# WaterTank.net
KiCad netlist of a schematic drawn in EasyEDA
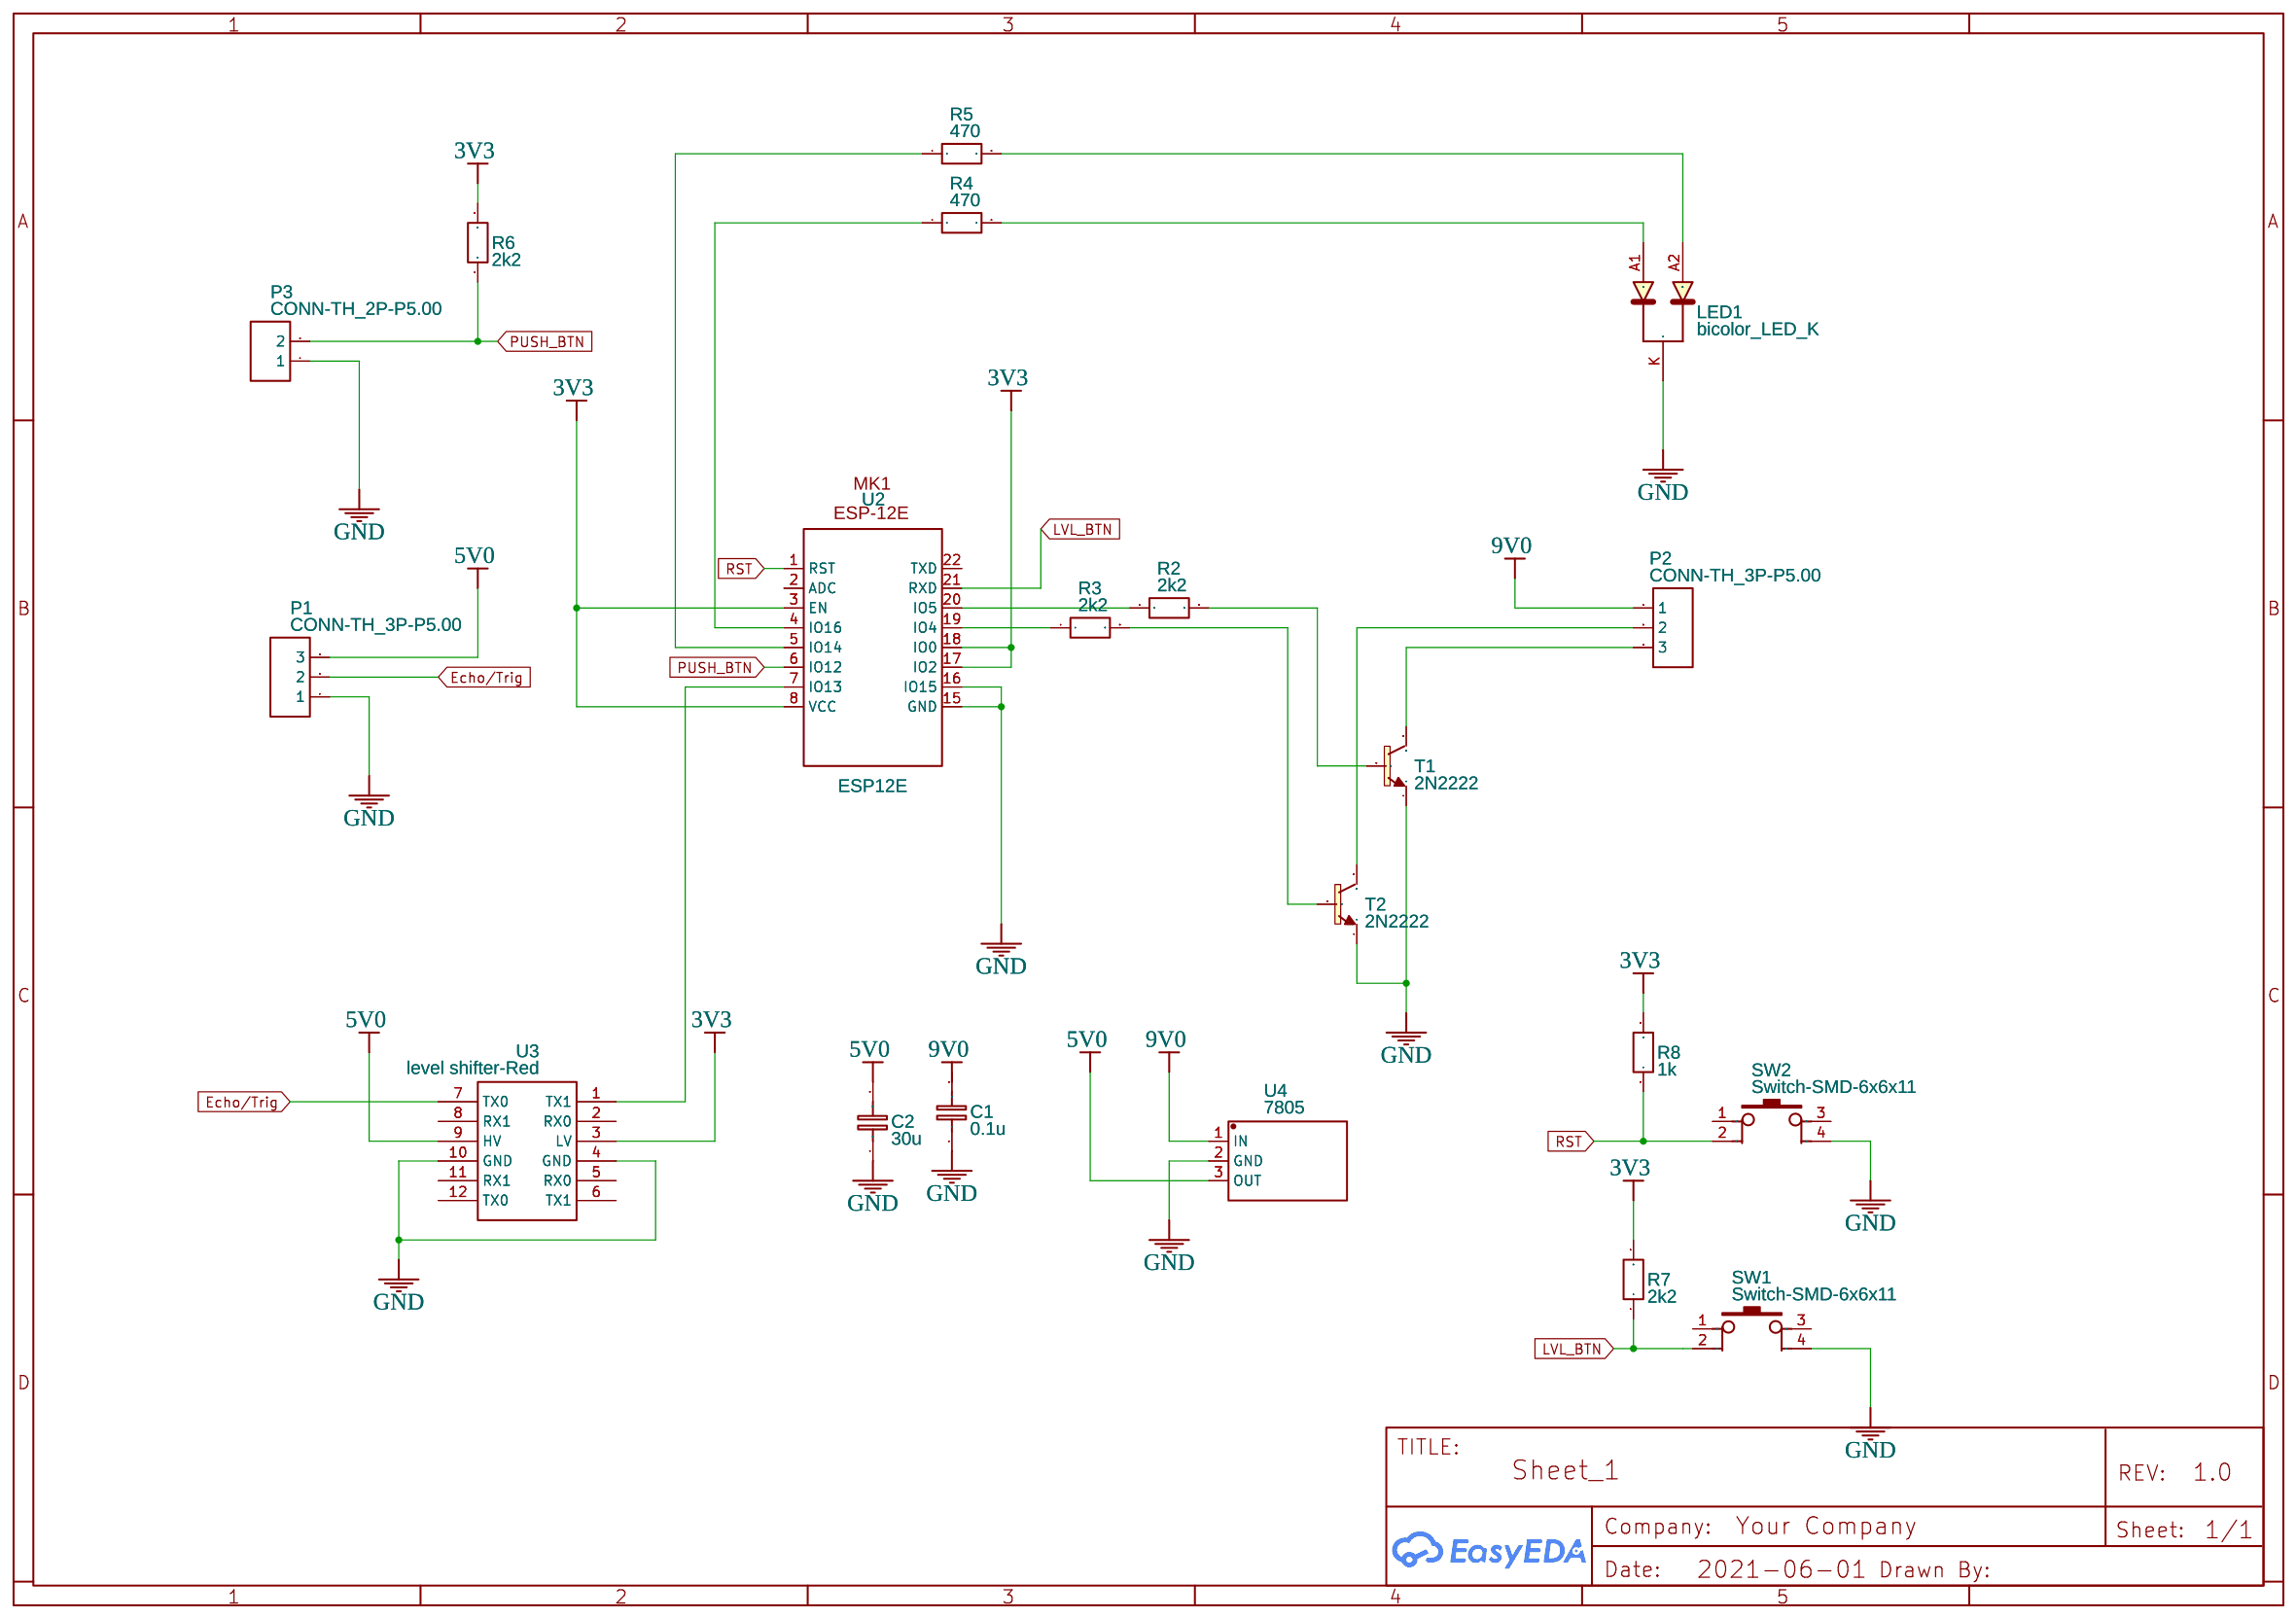
[diagram p0: Main]
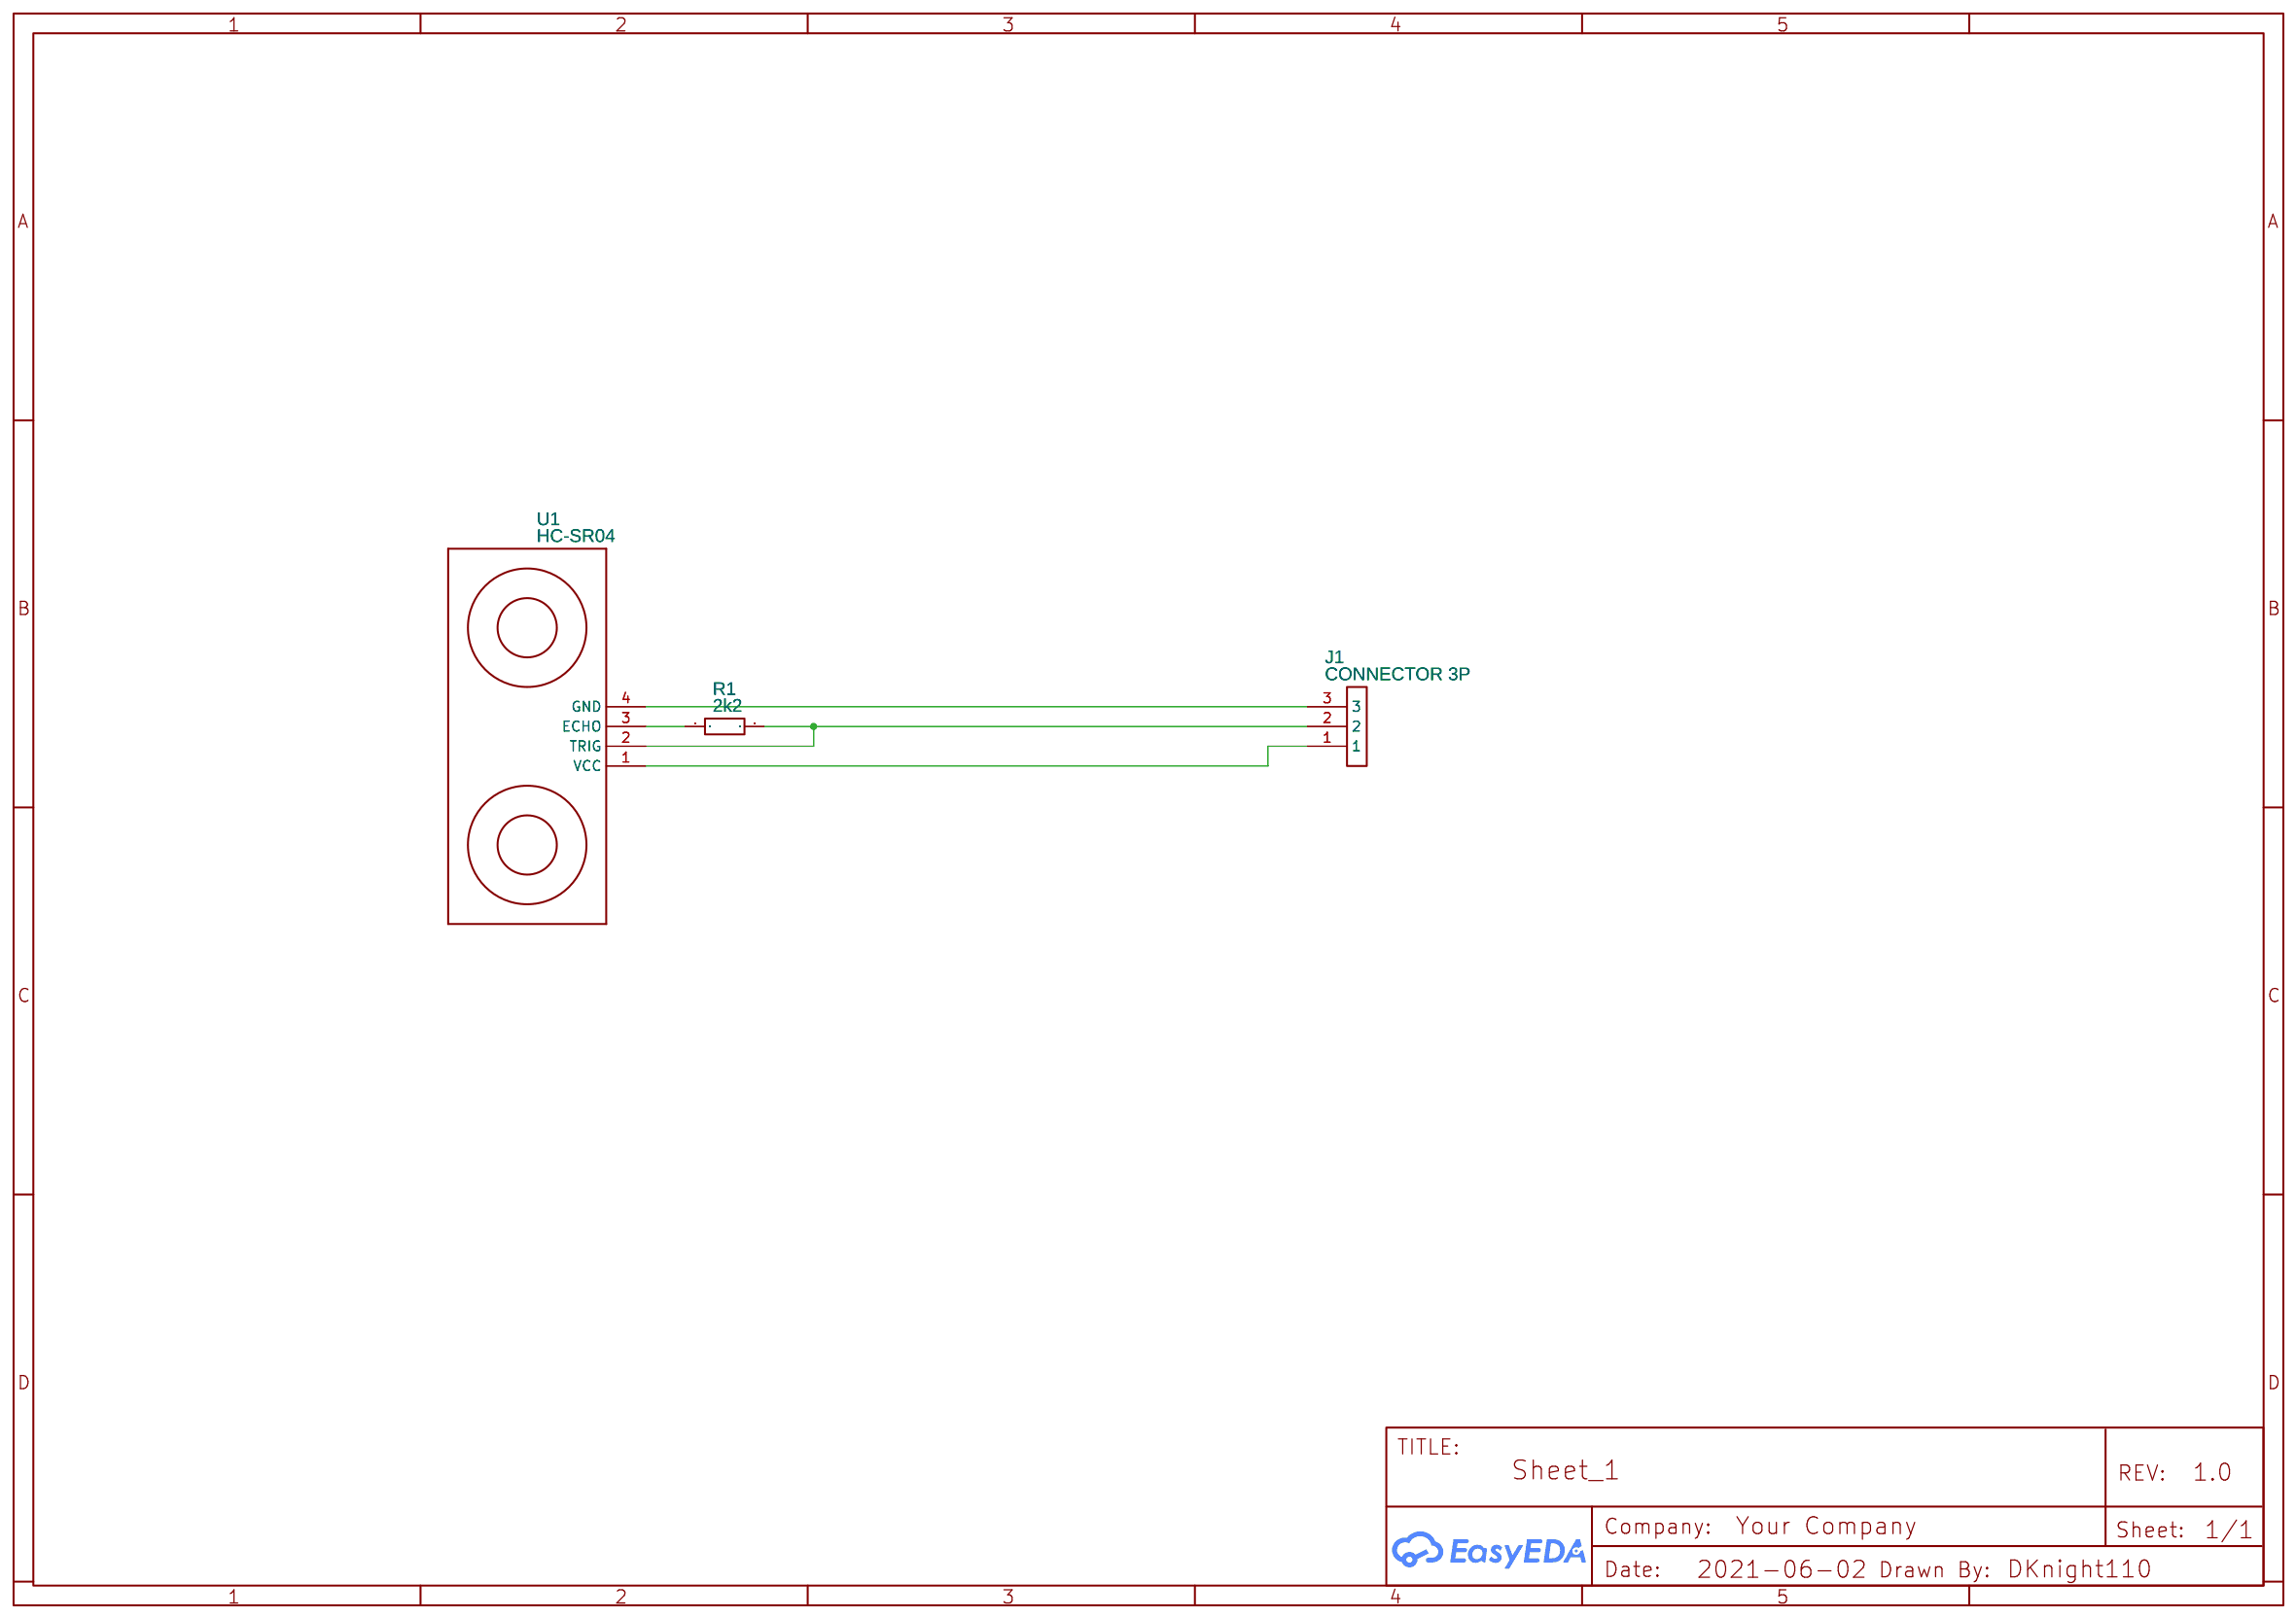
[diagram p1: Water Level Sensor]

(export (version "E")
  (design (tool "Eeschema 10.0.6"))
  (components
    (comp (ref "C1") (value "0.1u") (libsource (lib "") (part "C_0603_EU")))
    (comp (ref "C2") (value "30u") (libsource (lib "") (part "C_0603_EU")))
    (comp (ref "LED1")
      (value "bicolor_LED_K")
      (fields (field (name "BOM_Manufacturer Part") "bicolor LED"))
      (libsource (lib "") (part "bicolor_LED_K"))
    )
    (comp (ref "P1") (value "CONN-TH_3P-P5.00") (libsource (lib "") (part "CONN-TH_3P-P5.00")))
    (comp (ref "P2") (value "CONN-TH_3P-P5.00") (libsource (lib "") (part "CONN-TH_3P-P5.00_1")))
    (comp (ref "P3") (value "CONN-TH_2P-P5.00") (libsource (lib "") (part "CONN-TH_2P-P5.00")))
    (comp (ref "R2") (value "2k2") (libsource (lib "") (part "R_0603_EU")))
    (comp (ref "R3") (value "2k2") (libsource (lib "") (part "R_0603_EU")))
    (comp (ref "R4") (value "470") (libsource (lib "") (part "R_0603_EU")))
    (comp (ref "R5") (value "470") (libsource (lib "") (part "R_0603_EU")))
    (comp (ref "R6") (value "2k2") (libsource (lib "") (part "R_0603_EU_1")))
    (comp (ref "R7") (value "2k2") (libsource (lib "") (part "R_0603_EU_1")))
    (comp (ref "R8") (value "1k") (libsource (lib "") (part "R_0603_EU_1")))
    (comp (ref "SW1")
      (value "Switch-SMD-6x6x11")
      (fields
        (field (name "BOM_Manufacturer Part") "Switch6*6*11")
        (field (name "BOM_Supplier Part") "C91998")
      )
      (libsource (lib "") (part "Switch-SMD-6x6x11"))
    )
    (comp (ref "SW2")
      (value "Switch-SMD-6x6x11")
      (fields
        (field (name "BOM_Manufacturer Part") "Switch6*6*11")
        (field (name "BOM_Supplier Part") "C91998")
      )
      (libsource (lib "") (part "Switch-SMD-6x6x11"))
    )
    (comp (ref "T1") (value "2N2222") (libsource (lib "") (part "2N2222")))
    (comp (ref "T2") (value "2N2222") (libsource (lib "") (part "2N2222")))
    (comp (ref "U2") (value "ESP12E") (libsource (lib "") (part "ESP12E")))
    (comp (ref "U3")
      (value "level shifter-Red")
      (fields (field (name "BOM_Manufacturer Part") "level shifter"))
      (libsource (lib "") (part "level shifter-Red"))
    )
    (comp (ref "U4")
      (value "7805")
      (fields (field (name "BOM_Supplier Part") "C305416"))
      (libsource (lib "") (part "7805"))
    )
    (comp (ref "J1") (value "CONNECTOR 3P") (libsource (lib "") (part "CONNECTOR 3P")))
    (comp (ref "R1")
      (value "2k2")
      (fields
        (field (name "BOM_Manufacturer Part") "CFR02SJ0220A10")
        (field (name "BOM_Supplier Part") "C69874")
      )
      (libsource (lib "") (part "2k2"))
    )
    (comp (ref "U1") (value "HC-SR04") (libsource (lib "") (part "HC-SR04")))
  )
  (nets
    (net (code "1") (name "3V3") (class "Default")
      (node (ref "R6") (pin "2") (pinfunction "2_2") (pintype "unspecified"))
      (node (ref "R7") (pin "2") (pinfunction "2_2") (pintype "unspecified"))
      (node (ref "R8") (pin "2") (pinfunction "2_2") (pintype "unspecified"))
      (node (ref "U2") (pin "17") (pinfunction "IO2_17") (pintype "unspecified"))
      (node (ref "U2") (pin "18") (pinfunction "IO0_18") (pintype "unspecified"))
      (node (ref "U2") (pin "3") (pinfunction "EN_3") (pintype "unspecified"))
      (node (ref "U2") (pin "8") (pinfunction "VCC_8") (pintype "unspecified"))
      (node (ref "U3") (pin "3") (pinfunction "LV_3") (pintype "unspecified"))
    )
    (net (code "2") (name "5V0") (class "Default")
      (node (ref "C2") (pin "2") (pinfunction "2_2") (pintype "unspecified"))
      (node (ref "P1") (pin "3") (pinfunction "3_3") (pintype "unspecified"))
      (node (ref "U3") (pin "9") (pinfunction "HV_9") (pintype "unspecified"))
      (node (ref "U4") (pin "3") (pinfunction "OUT_3") (pintype "unspecified"))
    )
    (net (code "3") (name "9V0") (class "Default")
      (node (ref "P2") (pin "1") (pinfunction "1_1") (pintype "unspecified"))
      (node (ref "U4") (pin "1") (pinfunction "IN_1") (pintype "unspecified"))
    )
    (net (code "4") (name "Echo{slash}Trig") (class "Default")
      (node (ref "P1") (pin "2") (pinfunction "2_2") (pintype "unspecified"))
      (node (ref "U3") (pin "7") (pinfunction "TX0_7") (pintype "unspecified"))
    )
    (net (code "5") (name "GND") (class "Default")
      (node (ref "C1") (pin "1") (pinfunction "1_1") (pintype "unspecified"))
      (node (ref "C2") (pin "1") (pinfunction "1_1") (pintype "unspecified"))
      (node (ref "LED1") (pin "K") (pinfunction "K_K") (pintype "unspecified"))
      (node (ref "P1") (pin "1") (pinfunction "1_1") (pintype "unspecified"))
      (node (ref "P3") (pin "1") (pinfunction "1_1") (pintype "unspecified"))
      (node (ref "SW1") (pin "4") (pinfunction "4_4") (pintype "input"))
      (node (ref "SW2") (pin "4") (pinfunction "4_4") (pintype "input"))
      (node (ref "T1") (pin "E") (pinfunction "E_E") (pintype "bidirectional"))
      (node (ref "T2") (pin "E") (pinfunction "E_E") (pintype "bidirectional"))
      (node (ref "U2") (pin "15") (pinfunction "GND_15") (pintype "unspecified"))
      (node (ref "U2") (pin "16") (pinfunction "IO15_16") (pintype "unspecified"))
      (node (ref "U3") (pin "10") (pinfunction "GND_10") (pintype "unspecified"))
      (node (ref "U3") (pin "4") (pinfunction "GND_4") (pintype "unspecified"))
      (node (ref "U4") (pin "2") (pinfunction "GND_2") (pintype "unspecified"))
    )
    (net (code "6") (name "LVL_BTN") (class "Default")
      (node (ref "R7") (pin "1") (pinfunction "1_1") (pintype "unspecified"))
      (node (ref "SW1") (pin "2") (pinfunction "2_2") (pintype "input"))
      (node (ref "U2") (pin "21") (pinfunction "RXD_21") (pintype "unspecified"))
    )
    (net (code "7") (name "Net-(LED1-PadA1)") (class "Default")
      (node (ref "LED1") (pin "A1") (pinfunction "A1_A1") (pintype "unspecified"))
      (node (ref "R4") (pin "2") (pinfunction "2_2") (pintype "unspecified"))
    )
    (net (code "8") (name "Net-(LED1-PadA2)") (class "Default")
      (node (ref "LED1") (pin "A2") (pinfunction "A2_A2") (pintype "unspecified"))
      (node (ref "R5") (pin "2") (pinfunction "2_2") (pintype "unspecified"))
    )
    (net (code "9") (name "Net-(P2-Pad2)") (class "Default")
      (node (ref "P2") (pin "2") (pinfunction "2_2") (pintype "unspecified"))
      (node (ref "T2") (pin "C") (pinfunction "C_C") (pintype "bidirectional"))
    )
    (net (code "10") (name "Net-(P2-Pad3)") (class "Default")
      (node (ref "P2") (pin "3") (pinfunction "3_3") (pintype "unspecified"))
      (node (ref "T1") (pin "C") (pinfunction "C_C") (pintype "bidirectional"))
    )
    (net (code "11") (name "Net-(R2-Pad2)") (class "Default")
      (node (ref "R2") (pin "2") (pinfunction "2_2") (pintype "unspecified"))
      (node (ref "T1") (pin "B") (pinfunction "B_B") (pintype "bidirectional"))
    )
    (net (code "12") (name "Net-(R3-Pad2)") (class "Default")
      (node (ref "R3") (pin "2") (pinfunction "2_2") (pintype "unspecified"))
      (node (ref "T2") (pin "B") (pinfunction "B_B") (pintype "bidirectional"))
    )
    (net (code "13") (name "Net-(U1-ECHO)") (class "Default")
      (node (ref "R1") (pin "1") (pinfunction "1_1") (pintype "input"))
      (node (ref "U1") (pin "3") (pinfunction "ECHO_3") (pintype "output"))
    )
    (net (code "14") (name "Net-(U1-GND)") (class "Default")
      (node (ref "J1") (pin "3") (pinfunction "3_3") (pintype "unspecified"))
      (node (ref "U1") (pin "4") (pinfunction "GND_4") (pintype "passive"))
    )
    (net (code "15") (name "Net-(U1-TRIG)") (class "Default")
      (node (ref "J1") (pin "2") (pinfunction "2_2") (pintype "unspecified"))
      (node (ref "R1") (pin "2") (pinfunction "2_2") (pintype "input"))
      (node (ref "U1") (pin "2") (pinfunction "TRIG_2") (pintype "input"))
    )
    (net (code "16") (name "Net-(U1-VCC)") (class "Default")
      (node (ref "J1") (pin "1") (pinfunction "1_1") (pintype "unspecified"))
      (node (ref "U1") (pin "1") (pinfunction "VCC_1") (pintype "passive"))
    )
    (net (code "17") (name "Net-(U2-IO4)") (class "Default")
      (node (ref "R3") (pin "1") (pinfunction "1_1") (pintype "unspecified"))
      (node (ref "U2") (pin "19") (pinfunction "IO4_19") (pintype "unspecified"))
    )
    (net (code "18") (name "Net-(U2-IO5)") (class "Default")
      (node (ref "R2") (pin "1") (pinfunction "1_1") (pintype "unspecified"))
      (node (ref "U2") (pin "20") (pinfunction "IO5_20") (pintype "unspecified"))
    )
    (net (code "19") (name "Net-(U2-IO13)") (class "Default")
      (node (ref "U2") (pin "7") (pinfunction "IO13_7") (pintype "unspecified"))
      (node (ref "U3") (pin "1") (pinfunction "TX1_1") (pintype "unspecified"))
    )
    (net (code "20") (name "Net-(U2-IO14)") (class "Default")
      (node (ref "R5") (pin "1") (pinfunction "1_1") (pintype "unspecified"))
      (node (ref "U2") (pin "5") (pinfunction "IO14_5") (pintype "unspecified"))
    )
    (net (code "21") (name "Net-(U2-IO16)") (class "Default")
      (node (ref "R4") (pin "1") (pinfunction "1_1") (pintype "unspecified"))
      (node (ref "U2") (pin "4") (pinfunction "IO16_4") (pintype "unspecified"))
    )
    (net (code "22") (name "PUSH_BTN") (class "Default")
      (node (ref "P3") (pin "2") (pinfunction "2_2") (pintype "unspecified"))
      (node (ref "R6") (pin "1") (pinfunction "1_1") (pintype "unspecified"))
      (node (ref "U2") (pin "6") (pinfunction "IO12_6") (pintype "unspecified"))
    )
    (net (code "23") (name "RST") (class "Default")
      (node (ref "R8") (pin "1") (pinfunction "1_1") (pintype "unspecified"))
      (node (ref "SW2") (pin "2") (pinfunction "2_2") (pintype "input"))
      (node (ref "U2") (pin "1") (pinfunction "RST_1") (pintype "unspecified"))
    )
    (net (code "24") (name "unconnected-(C1-Pad2)") (class "Default")
      (node (ref "C1") (pin "2") (pinfunction "2_2") (pintype "unspecified"))
    )
    (net (code "25") (name "unconnected-(SW1-Pad1)") (class "Default")
      (node (ref "SW1") (pin "1") (pinfunction "1_1") (pintype "input"))
    )
    (net (code "26") (name "unconnected-(SW1-Pad3)") (class "Default")
      (node (ref "SW1") (pin "3") (pinfunction "3_3") (pintype "input"))
    )
    (net (code "27") (name "unconnected-(SW2-Pad1)") (class "Default")
      (node (ref "SW2") (pin "1") (pinfunction "1_1") (pintype "input"))
    )
    (net (code "28") (name "unconnected-(SW2-Pad3)") (class "Default")
      (node (ref "SW2") (pin "3") (pinfunction "3_3") (pintype "input"))
    )
    (net (code "29") (name "unconnected-(U2-ADC-Pad2)") (class "Default")
      (node (ref "U2") (pin "2") (pinfunction "ADC_2") (pintype "unspecified"))
    )
    (net (code "30") (name "unconnected-(U2-TXD-Pad22)") (class "Default")
      (node (ref "U2") (pin "22") (pinfunction "TXD_22") (pintype "unspecified"))
    )
    (net (code "31") (name "unconnected-(U3-RX0-Pad2)") (class "Default")
      (node (ref "U3") (pin "2") (pinfunction "RX0_2") (pintype "unspecified"))
    )
    (net (code "32") (name "unconnected-(U3-RX0-Pad5)") (class "Default")
      (node (ref "U3") (pin "5") (pinfunction "RX0_5") (pintype "unspecified"))
    )
    (net (code "33") (name "unconnected-(U3-RX1-Pad8)") (class "Default")
      (node (ref "U3") (pin "8") (pinfunction "RX1_8") (pintype "unspecified"))
    )
    (net (code "34") (name "unconnected-(U3-RX1-Pad11)") (class "Default")
      (node (ref "U3") (pin "11") (pinfunction "RX1_11") (pintype "unspecified"))
    )
    (net (code "35") (name "unconnected-(U3-TX0-Pad12)") (class "Default")
      (node (ref "U3") (pin "12") (pinfunction "TX0_12") (pintype "unspecified"))
    )
    (net (code "36") (name "unconnected-(U3-TX1-Pad6)") (class "Default")
      (node (ref "U3") (pin "6") (pinfunction "TX1_6") (pintype "unspecified"))
    )
  )
)
